# LabPowerSupply_CurrentModuleV1_1.net
KiCad netlist of a schematic drawn in EAGLE
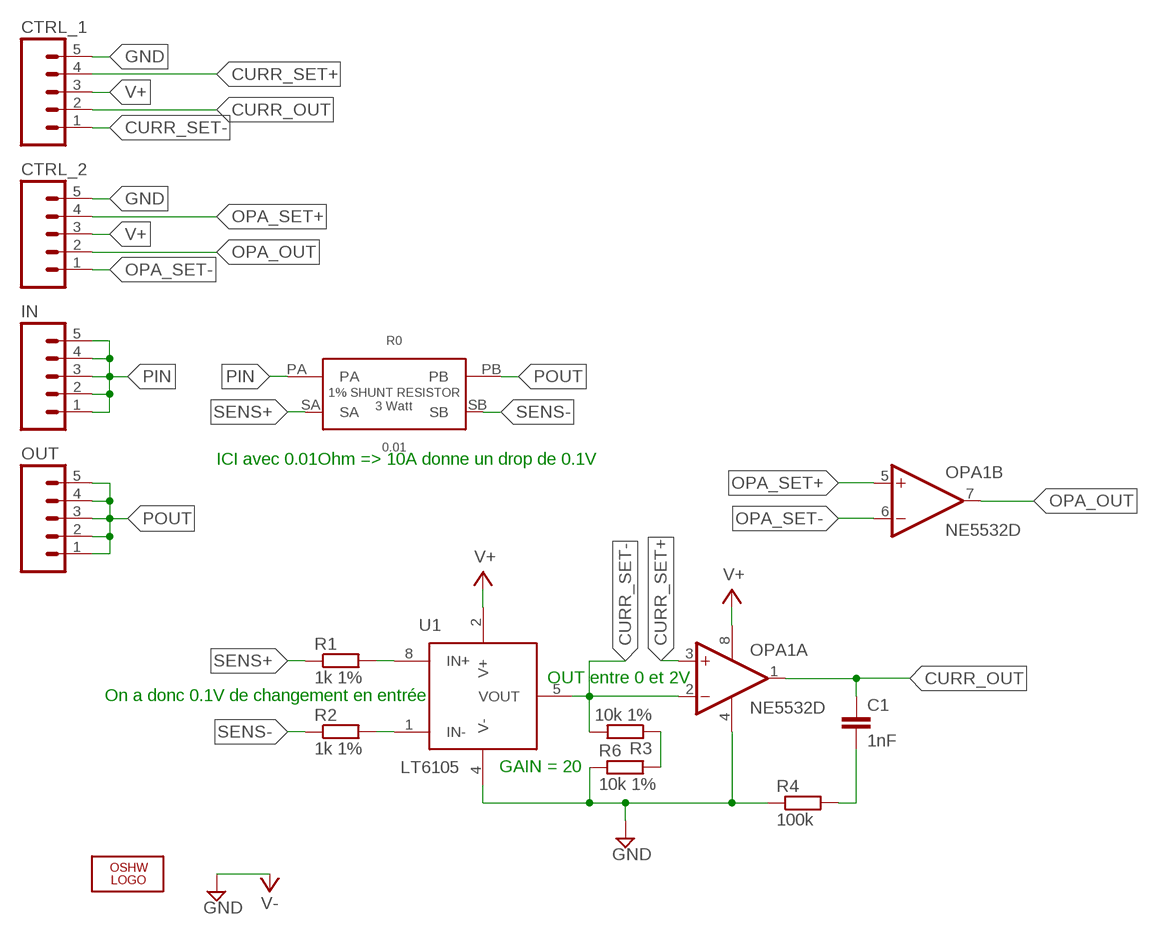
[diagram p0: schematic, sheet 1]

(export (version "E")
  (design (tool "Eeschema 10.0.6"))
  (components
    (comp (ref "C1")
      (value "1nF")
      (footprint "eagle-import:C1206K")
      (libsource (lib "eagle-import") (part "C-EUC1206K"))
    )
    (comp (ref "CTRL_1")
      (value "M05PTH_LONGPADS")
      (footprint "eagle-import:1X05_LONGPADS")
      (libsource (lib "eagle-import") (part "M05PTH_LONGPADS"))
    )
    (comp (ref "CTRL_2")
      (value "M05PTH_LONGPADS")
      (footprint "eagle-import:1X05_LONGPADS")
      (libsource (lib "eagle-import") (part "M05PTH_LONGPADS"))
    )
    (comp (ref "IN")
      (value "M05PTH_LONGPADS")
      (footprint "eagle-import:1X05_LONGPADS")
      (libsource (lib "eagle-import") (part "M05PTH_LONGPADS"))
    )
    (comp (ref "LOGO1")
      (value "OSHW_LOGO_FILLX0150-NT")
      (footprint "eagle-import:OSHW_FILLX150_NOTEXT")
      (libsource (lib "eagle-import") (part "OSHW_LOGO_FILLX0150-NT"))
    )
    (comp (ref "OPA1")
      (value "NE5532D")
      (footprint "eagle-import:SO08")
      (libsource (lib "eagle-import") (part "NE5532D"))
    )
    (comp (ref "OUT")
      (value "M05PTH_LONGPADS")
      (footprint "eagle-import:1X05_LONGPADS")
      (libsource (lib "eagle-import") (part "M05PTH_LONGPADS"))
    )
    (comp (ref "R0")
      (value "0.01")
      (footprint "eagle-import:3637R")
      (libsource (lib "eagle-import") (part "WSL3637R0100FEA"))
    )
    (comp (ref "R1")
      (value "1k 1%")
      (footprint "eagle-import:R1206")
      (libsource (lib "eagle-import") (part "R-EU_R1206"))
    )
    (comp (ref "R2")
      (value "1k 1%")
      (footprint "eagle-import:R1206")
      (libsource (lib "eagle-import") (part "R-EU_R1206"))
    )
    (comp (ref "R3")
      (value "10k 1%")
      (footprint "eagle-import:R1206")
      (libsource (lib "eagle-import") (part "R-EU_R1206"))
    )
    (comp (ref "R4")
      (value "100k")
      (footprint "eagle-import:R1206")
      (libsource (lib "eagle-import") (part "R-EU_R1206"))
    )
    (comp (ref "R6")
      (value "10k 1%")
      (footprint "eagle-import:R1206")
      (libsource (lib "eagle-import") (part "R-EU_R1206"))
    )
    (comp (ref "U1")
      (value "LT6105")
      (footprint "eagle-import:MSOP_8")
      (libsource (lib "eagle-import") (part "LT6105"))
    )
  )
  (nets
    (net (code "1") (name "CURR_OUT") (class "Default")
      (node (ref "C1") (pin "1") (pinfunction "1_1") (pintype "passive"))
      (node (ref "CTRL_1") (pin "2") (pinfunction "2_2") (pintype "passive"))
      (node (ref "OPA1") (pin "1") (pinfunction "OUT_1") (pintype "output"))
    )
    (net (code "2") (name "CURR_SET+") (class "Default")
      (node (ref "CTRL_1") (pin "4") (pinfunction "4_4") (pintype "passive"))
      (node (ref "OPA1") (pin "3") (pinfunction "+IN_3") (pintype "input"))
    )
    (net (code "3") (name "CURR_SET-") (class "Default")
      (node (ref "CTRL_1") (pin "1") (pinfunction "1_1") (pintype "passive"))
      (node (ref "OPA1") (pin "2") (pinfunction "-IN_2") (pintype "input"))
      (node (ref "R3") (pin "2") (pinfunction "2_2") (pintype "passive"))
      (node (ref "U1") (pin "5") (pinfunction "VOUT_5") (pintype "output"))
    )
    (net (code "4") (name "GND") (class "Default")
      (node (ref "CTRL_1") (pin "5") (pinfunction "5_5") (pintype "passive"))
      (node (ref "CTRL_2") (pin "5") (pinfunction "5_5") (pintype "passive"))
      (node (ref "OPA1") (pin "4") (pinfunction "V-_4") (pintype "power_in"))
      (node (ref "R4") (pin "1") (pinfunction "1_1") (pintype "passive"))
      (node (ref "R6") (pin "1") (pinfunction "1_1") (pintype "passive"))
      (node (ref "U1") (pin "4") (pinfunction "V-_4") (pintype "power_in"))
    )
    (net (code "5") (name "Net-(C1-Pad2)") (class "Default")
      (node (ref "C1") (pin "2") (pinfunction "2_2") (pintype "passive"))
      (node (ref "R4") (pin "2") (pinfunction "2_2") (pintype "passive"))
    )
    (net (code "6") (name "Net-(R3-Pad1)") (class "Default")
      (node (ref "R3") (pin "1") (pinfunction "1_1") (pintype "passive"))
      (node (ref "R6") (pin "2") (pinfunction "2_2") (pintype "passive"))
    )
    (net (code "7") (name "Net-(U1-IN+)") (class "Default")
      (node (ref "R1") (pin "2") (pinfunction "2_2") (pintype "passive"))
      (node (ref "U1") (pin "8") (pinfunction "IN+_8") (pintype "input"))
    )
    (net (code "8") (name "Net-(U1-IN-)") (class "Default")
      (node (ref "R2") (pin "2") (pinfunction "2_2") (pintype "passive"))
      (node (ref "U1") (pin "1") (pinfunction "IN-_1") (pintype "input"))
    )
    (net (code "9") (name "OPA_OUT") (class "Default")
      (node (ref "CTRL_2") (pin "2") (pinfunction "2_2") (pintype "passive"))
      (node (ref "OPA1") (pin "7") (pinfunction "OUT_7") (pintype "output"))
    )
    (net (code "10") (name "OPA_SET+") (class "Default")
      (node (ref "CTRL_2") (pin "4") (pinfunction "4_4") (pintype "passive"))
      (node (ref "OPA1") (pin "5") (pinfunction "+IN_5") (pintype "input"))
    )
    (net (code "11") (name "OPA_SET-") (class "Default")
      (node (ref "CTRL_2") (pin "1") (pinfunction "1_1") (pintype "passive"))
      (node (ref "OPA1") (pin "6") (pinfunction "-IN_6") (pintype "input"))
    )
    (net (code "12") (name "PIN") (class "Default")
      (node (ref "IN") (pin "1") (pinfunction "1_1") (pintype "passive"))
      (node (ref "IN") (pin "2") (pinfunction "2_2") (pintype "passive"))
      (node (ref "IN") (pin "3") (pinfunction "3_3") (pintype "passive"))
      (node (ref "IN") (pin "4") (pinfunction "4_4") (pintype "passive"))
      (node (ref "IN") (pin "5") (pinfunction "5_5") (pintype "passive"))
      (node (ref "R0") (pin "PA") (pinfunction "PA_PA") (pintype "bidirectional"))
    )
    (net (code "13") (name "POUT") (class "Default")
      (node (ref "OUT") (pin "1") (pinfunction "1_1") (pintype "passive"))
      (node (ref "OUT") (pin "2") (pinfunction "2_2") (pintype "passive"))
      (node (ref "OUT") (pin "3") (pinfunction "3_3") (pintype "passive"))
      (node (ref "OUT") (pin "4") (pinfunction "4_4") (pintype "passive"))
      (node (ref "OUT") (pin "5") (pinfunction "5_5") (pintype "passive"))
      (node (ref "R0") (pin "PB") (pinfunction "PB_PB") (pintype "bidirectional"))
    )
    (net (code "14") (name "SENS+") (class "Default")
      (node (ref "R0") (pin "SA") (pinfunction "SA_SA") (pintype "bidirectional"))
      (node (ref "R1") (pin "1") (pinfunction "1_1") (pintype "passive"))
    )
    (net (code "15") (name "SENS-") (class "Default")
      (node (ref "R0") (pin "SB") (pinfunction "SB_SB") (pintype "bidirectional"))
      (node (ref "R2") (pin "1") (pinfunction "1_1") (pintype "passive"))
    )
    (net (code "16") (name "V+") (class "Default")
      (node (ref "CTRL_1") (pin "3") (pinfunction "3_3") (pintype "passive"))
      (node (ref "CTRL_2") (pin "3") (pinfunction "3_3") (pintype "passive"))
      (node (ref "OPA1") (pin "8") (pinfunction "V+_8") (pintype "power_in"))
      (node (ref "U1") (pin "2") (pinfunction "V+_2") (pintype "power_in"))
    )
  )
)
